# powerSupply.net
KiCad netlist of a schematic drawn in Altium Designer
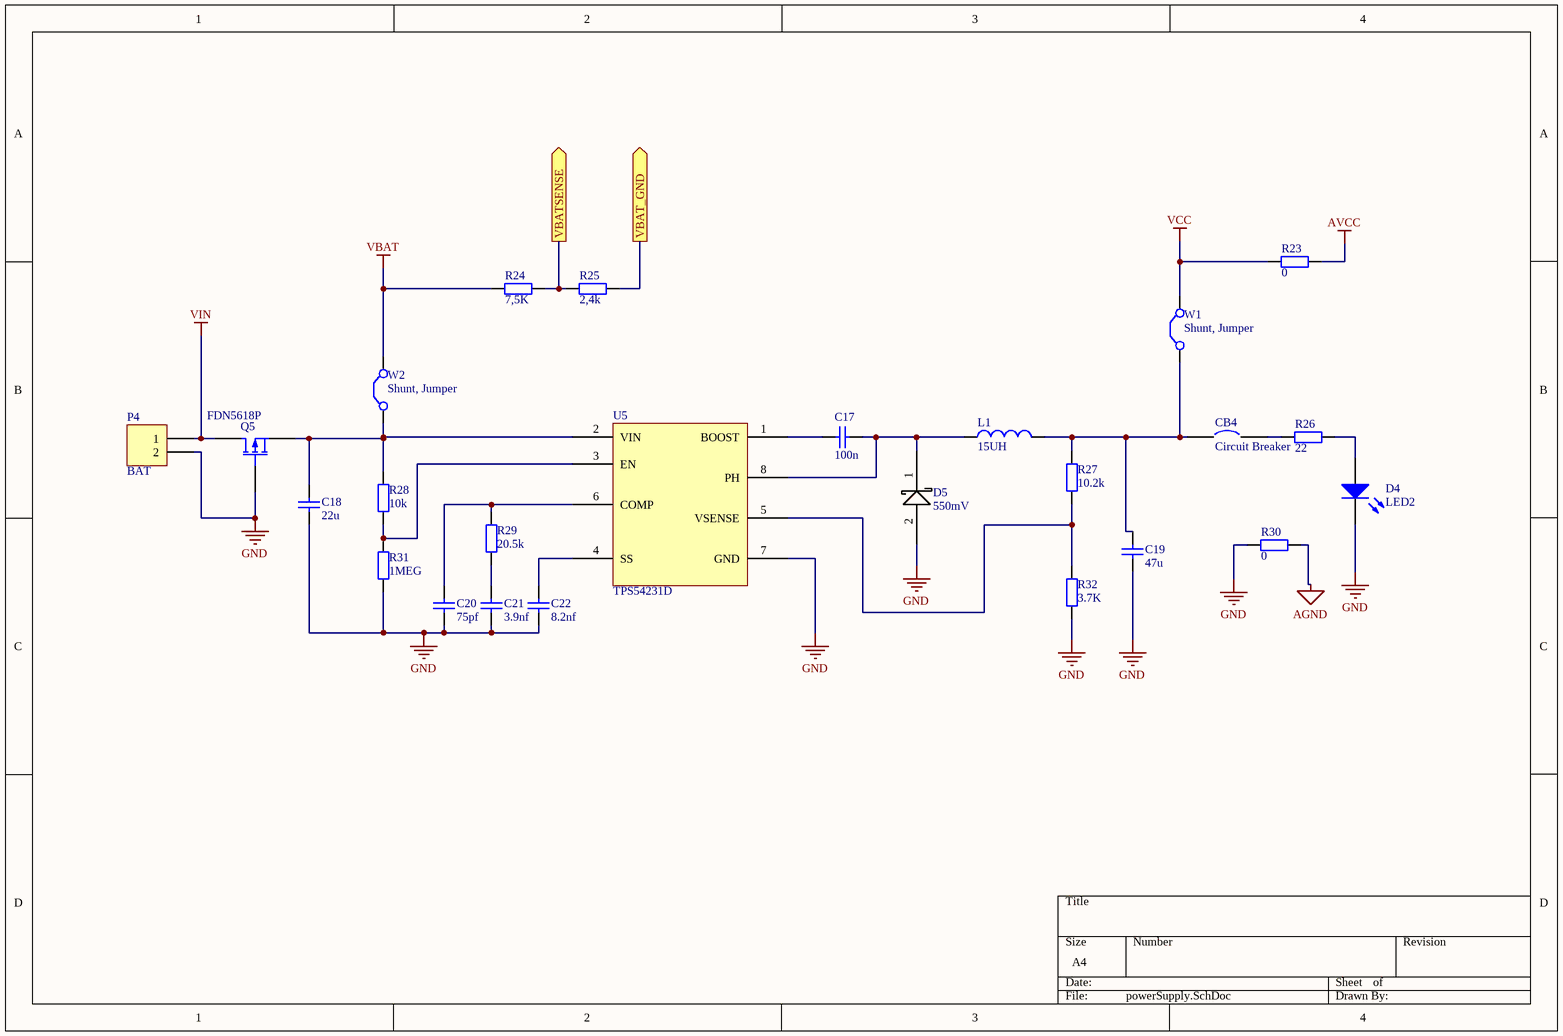
[diagram p0: powerSupply.SchDoc]

(export (version "E")
  (design (tool "Eeschema 10.0.6"))
  (components
    (comp (ref "C17")
      (value "100n")
      (footprint "CAP 0603/1608")
      (libsource (lib "Miscellaneous Devices") (part "Cap"))
    )
    (comp (ref "C18")
      (value "22u")
      (footprint "CAP 0603/1608")
      (libsource (lib "Miscellaneous Devices") (part "Cap"))
    )
    (comp (ref "C19")
      (value "47u")
      (footprint "CAP 1210/3225 - 2.5MM")
      (description "Condensateur céramique multicouche CMS, 1210 [3225 Metric], 47 µF, 16 V, ± 20%, X5R, Série GRM")
      (libsource (lib "Miscellaneous Devices") (part "Cap"))
    )
    (comp (ref "C20")
      (value "75pf")
      (footprint "CAP 0603/1608")
      (libsource (lib "Miscellaneous Devices") (part "Cap"))
    )
    (comp (ref "C21")
      (value "3.9nf")
      (footprint "CAP 0603/1608")
      (libsource (lib "Miscellaneous Devices") (part "Cap"))
    )
    (comp (ref "C22")
      (value "8.2nf")
      (footprint "CAP 0603/1608")
      (libsource (lib "Miscellaneous Devices") (part "Cap"))
    )
    (comp (ref "CB4")
      (value "Circuit Breaker")
      (footprint "JUMPER PAD")
      (libsource (lib "Miscellaneous Devices") (part "Circuit Breaker"))
    )
    (comp (ref "D4")
      (value "LED2")
      (footprint "LED 0603/1608 BLUE")
      (description "LED, Bleu, CMS, 0.8mm x 1.6mm, 5 mA, 2.9 V, 470 nm")
      (libsource (lib "Miscellaneous Devices") (part "LED2"))
    )
    (comp (ref "D5")
      (value "550mV")
      (footprint "microSMA")
      (description "TAIWAN SEMICONDUCTOR  SS14M  Redresseur Schottky, 40 V, 1 A, Une, MicroSMA, 2 Broche(s), 550 mV")
      (libsource (lib "CompoLib") (part "schottky"))
    )
    (comp (ref "L1")
      (value "15UH")
      (footprint "SRN6045-3R3Y")
      (description "BOURNS  SRN6045-150M  Inductance de puissance CMS, 15 µH, 1.9 A, 2.3 A, Blindé, 0.0958 ohm")
      (libsource (lib "Miscellaneous Devices") (part "Inductor"))
    )
    (comp (ref "P4")
      (value "BAT")
      (footprint "HDR1X2")
      (description "Header, 2-Pin")
      (fields (field (name "PUBLISHER") "Altium Limited"))
      (libsource (lib "Miscellaneous Connectors") (part "Header 2"))
    )
    (comp (ref "Q5")
      (value "FDN5618P")
      (footprint "SOT-23_M")
      (description "Transistor MOSFET, Canal P, -1.25 A, -60 V, 170 mohm, -10 V, 20 V")
      (libsource (lib "Miscellaneous Devices") (part "MOSFET-P"))
    )
    (comp (ref "R23")
      (value "0")
      (footprint "RES 0603/1608")
      (libsource (lib "Miscellaneous Devices") (part "Res2"))
    )
    (comp (ref "R24") (value "7,5K") (footprint "RES 0603/1608") (libsource (lib "") (part "Res2_2")))
    (comp (ref "R25") (value "2,4k") (footprint "RES 0603/1608") (libsource (lib "") (part "Res2_2")))
    (comp (ref "R26")
      (value "22")
      (footprint "RES 0603/1608")
      (libsource (lib "Miscellaneous Devices") (part "Res2"))
    )
    (comp (ref "R27") (value "10.2k") (footprint "RES 0603/1608") (libsource (lib "") (part "Res2_1")))
    (comp (ref "R28") (value "10k") (footprint "RES 0603/1608") (libsource (lib "") (part "Res2_1")))
    (comp (ref "R29") (value "20.5k") (footprint "RES 0603/1608") (libsource (lib "") (part "Res2_1")))
    (comp (ref "R30")
      (value "0")
      (footprint "RES 0603/1608")
      (libsource (lib "Miscellaneous Devices") (part "Res2"))
    )
    (comp (ref "R31") (value "1MEG") (footprint "RES 0603/1608") (libsource (lib "") (part "Res2_1")))
    (comp (ref "R32") (value "3.7K") (footprint "RES 0603/1608") (libsource (lib "") (part "Res2_1")))
    (comp (ref "U5") (value "TPS54231D") (footprint "SOIC8") (libsource (lib "CompoLib") (part "TPS54231D")))
    (comp (ref "W1")
      (value "Shunt, Jumper")
      (footprint "HDR1X2")
      (description "Jumper Socket, Pin Headers, 2 Voies, 1.27 mm")
      (libsource (lib "Miscellaneous Devices") (part "Jumper"))
    )
    (comp (ref "W2")
      (value "Shunt, Jumper")
      (footprint "HDR1X2")
      (description "Jumper Socket, Pin Headers, 2 Voies, 1.27 mm")
      (libsource (lib "Miscellaneous Devices") (part "Jumper"))
    )
  )
  (nets
    (net (code "1") (name "/VBATSENSE") (class "Default")
      (node (ref "R24") (pin "1") (pinfunction "1_1") (pintype "passive"))
      (node (ref "R25") (pin "2") (pinfunction "2_2") (pintype "passive"))
    )
    (net (code "2") (name "/VBAT_GND") (class "Default")
      (node (ref "R25") (pin "1") (pinfunction "1_1") (pintype "passive"))
    )
    (net (code "3") (name "AGND") (class "Default")
      (node (ref "R30") (pin "2") (pinfunction "2_2") (pintype "passive"))
    )
    (net (code "4") (name "AVCC") (class "Default")
      (node (ref "R23") (pin "2") (pinfunction "2_2") (pintype "passive"))
    )
    (net (code "5") (name "GND") (class "Default")
      (node (ref "C18") (pin "2") (pinfunction "2_2") (pintype "passive"))
      (node (ref "C19") (pin "2") (pinfunction "2_2") (pintype "passive"))
      (node (ref "C20") (pin "2") (pinfunction "2_2") (pintype "passive"))
      (node (ref "C21") (pin "2") (pinfunction "2_2") (pintype "passive"))
      (node (ref "C22") (pin "2") (pinfunction "2_2") (pintype "passive"))
      (node (ref "D4") (pin "2") (pinfunction "K_2") (pintype "passive"))
      (node (ref "D5") (pin "2") (pintype "passive"))
      (node (ref "P4") (pin "2") (pinfunction "2_2") (pintype "passive"))
      (node (ref "Q5") (pin "2") (pinfunction "G_2") (pintype "passive"))
      (node (ref "R30") (pin "1") (pinfunction "1_1") (pintype "passive"))
      (node (ref "R31") (pin "1") (pinfunction "1_1") (pintype "passive"))
      (node (ref "R32") (pin "1") (pinfunction "1_1") (pintype "passive"))
      (node (ref "U5") (pin "7") (pinfunction "GND_7") (pintype "passive"))
    )
    (net (code "6") (name "Net-(C21-Pad1)") (class "Default")
      (node (ref "C21") (pin "1") (pinfunction "1_1") (pintype "passive"))
      (node (ref "R29") (pin "1") (pinfunction "1_1") (pintype "passive"))
    )
    (net (code "7") (name "Net-(CB4-Pad2)") (class "Default")
      (node (ref "CB4") (pin "2") (pinfunction "2_2") (pintype "passive"))
      (node (ref "R26") (pin "1") (pinfunction "1_1") (pintype "passive"))
    )
    (net (code "8") (name "Net-(D4-A)") (class "Default")
      (node (ref "D4") (pin "1") (pinfunction "A_1") (pintype "passive"))
      (node (ref "R26") (pin "2") (pinfunction "2_2") (pintype "passive"))
    )
    (net (code "9") (name "Net-(Q5-S)") (class "Default")
      (node (ref "C18") (pin "1") (pinfunction "1_1") (pintype "passive"))
      (node (ref "Q5") (pin "3") (pinfunction "S_3") (pintype "passive"))
      (node (ref "R28") (pin "2") (pinfunction "2_2") (pintype "passive"))
      (node (ref "U5") (pin "2") (pinfunction "VIN_2") (pintype "passive"))
      (node (ref "W2") (pin "1") (pinfunction "C1_1") (pintype "passive"))
    )
    (net (code "10") (name "Net-(U5-BOOST)") (class "Default")
      (node (ref "C17") (pin "1") (pinfunction "1_1") (pintype "passive"))
      (node (ref "U5") (pin "1") (pinfunction "BOOST_1") (pintype "passive"))
    )
    (net (code "11") (name "Net-(U5-COMP)") (class "Default")
      (node (ref "C20") (pin "1") (pinfunction "1_1") (pintype "passive"))
      (node (ref "R29") (pin "2") (pinfunction "2_2") (pintype "passive"))
      (node (ref "U5") (pin "6") (pinfunction "COMP_6") (pintype "passive"))
    )
    (net (code "12") (name "Net-(U5-EN)") (class "Default")
      (node (ref "R28") (pin "1") (pinfunction "1_1") (pintype "passive"))
      (node (ref "R31") (pin "2") (pinfunction "2_2") (pintype "passive"))
      (node (ref "U5") (pin "3") (pinfunction "EN_3") (pintype "passive"))
    )
    (net (code "13") (name "Net-(U5-PH)") (class "Default")
      (node (ref "C17") (pin "2") (pinfunction "2_2") (pintype "passive"))
      (node (ref "D5") (pin "1") (pintype "passive"))
      (node (ref "L1") (pin "1") (pinfunction "1_1") (pintype "passive"))
      (node (ref "U5") (pin "8") (pinfunction "PH_8") (pintype "passive"))
    )
    (net (code "14") (name "Net-(U5-SS)") (class "Default")
      (node (ref "C22") (pin "1") (pinfunction "1_1") (pintype "passive"))
      (node (ref "U5") (pin "4") (pinfunction "SS_4") (pintype "passive"))
    )
    (net (code "15") (name "Net-(U5-VSENSE)") (class "Default")
      (node (ref "R27") (pin "1") (pinfunction "1_1") (pintype "passive"))
      (node (ref "R32") (pin "2") (pinfunction "2_2") (pintype "passive"))
      (node (ref "U5") (pin "5") (pinfunction "VSENSE_5") (pintype "passive"))
    )
    (net (code "16") (name "Net-(W1-C1)") (class "Default")
      (node (ref "C19") (pin "1") (pinfunction "1_1") (pintype "passive"))
      (node (ref "CB4") (pin "1") (pinfunction "1_1") (pintype "passive"))
      (node (ref "L1") (pin "2") (pinfunction "2_2") (pintype "passive"))
      (node (ref "R27") (pin "2") (pinfunction "2_2") (pintype "passive"))
      (node (ref "W1") (pin "1") (pinfunction "C1_1") (pintype "passive"))
    )
    (net (code "17") (name "VBAT") (class "Default")
      (node (ref "R24") (pin "2") (pinfunction "2_2") (pintype "passive"))
      (node (ref "W2") (pin "2") (pinfunction "C2_2") (pintype "passive"))
    )
    (net (code "18") (name "VCC") (class "Default")
      (node (ref "R23") (pin "1") (pinfunction "1_1") (pintype "passive"))
      (node (ref "W1") (pin "2") (pinfunction "C2_2") (pintype "passive"))
    )
    (net (code "19") (name "VIN") (class "Default")
      (node (ref "P4") (pin "1") (pinfunction "1_1") (pintype "passive"))
      (node (ref "Q5") (pin "1") (pinfunction "D_1") (pintype "passive"))
    )
  )
)
